# ETHERNET.net
KiCad netlist of a schematic drawn in Altium Designer
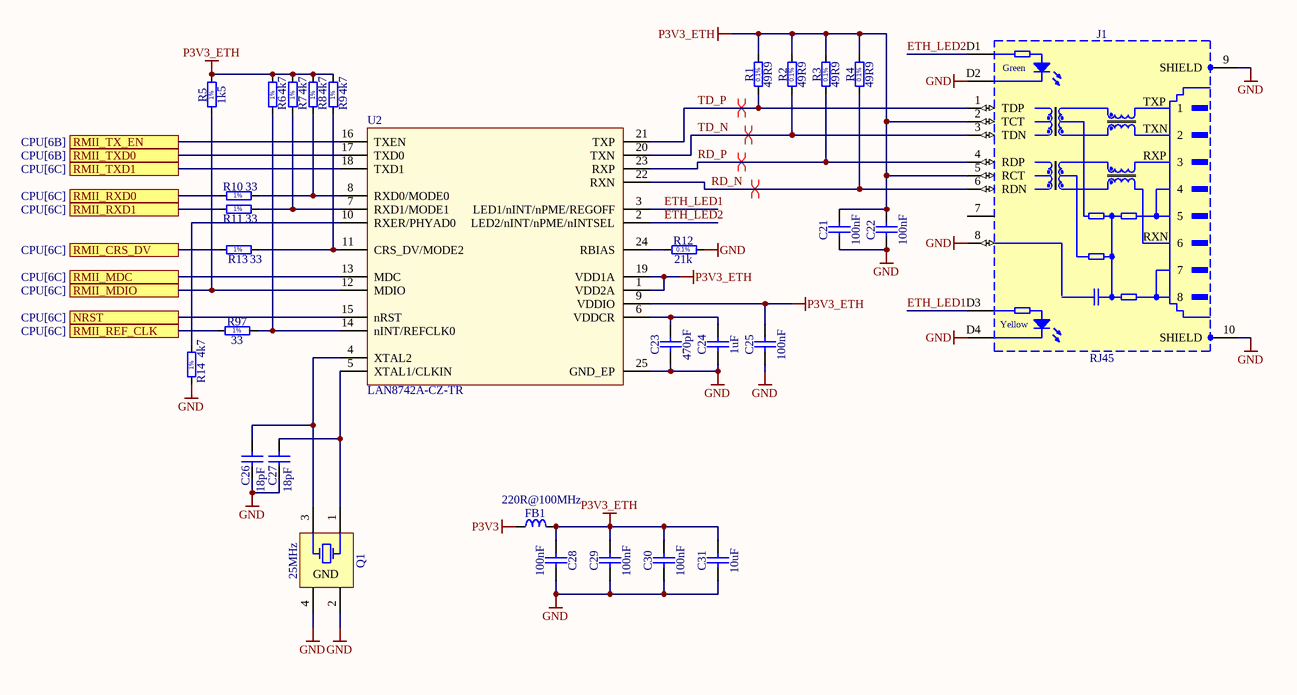
[diagram p0: ETHERNET.SchDoc]

(export (version "E")
  (design (tool "Eeschema 10.0.6"))
  (components
    (comp (ref "C21")
      (value "100nF")
      (footprint "CAPC1005X55N")
      (description "Non-polarised capacitor")
      (fields
        (field (name "PART NUMBER") "CC0402_100NF_16V_10%_X5R")
        (field (name "VOLTAGE") "16V")
        (field (name "AUTHOR") "CERN DEM JLC")
      )
      (libsource (lib "Capacitors") (part "Capacitor - non polarized"))
    )
    (comp (ref "C22")
      (value "100nF")
      (footprint "CAPC1005X55N")
      (description "Non-polarised capacitor")
      (fields
        (field (name "PART NUMBER") "CC0402_100NF_16V_10%_X5R")
        (field (name "VOLTAGE") "16V")
        (field (name "AUTHOR") "CERN DEM JLC")
      )
      (libsource (lib "Capacitors") (part "Capacitor - non polarized"))
    )
    (comp (ref "C23")
      (value "470pF")
      (footprint "CAPC1005X55N")
      (description "Non-polarised capacitor")
      (fields
        (field (name "PART NUMBER") "CC0402_470PF_50V_10%_X7R")
        (field (name "VOLTAGE") "50V")
        (field (name "AUTHOR") "CERN DEM JLC")
      )
      (libsource (lib "Capacitors") (part "Capacitor - non polarized"))
    )
    (comp (ref "C24")
      (value "1uF")
      (footprint "CAPC1005X55N")
      (description "Non-polarised capacitor")
      (fields
        (field (name "PART NUMBER") "CC0402_1UF_16V_10%_X5R")
        (field (name "VOLTAGE") "16V")
        (field (name "AUTHOR") "CERN DEM JLC")
      )
      (libsource (lib "Capacitors") (part "Capacitor - non polarized"))
    )
    (comp (ref "C25")
      (value "100nF")
      (footprint "CAPC1005X55N")
      (description "Non-polarised capacitor")
      (fields
        (field (name "PART NUMBER") "CC0402_100NF_16V_10%_X5R")
        (field (name "VOLTAGE") "16V")
        (field (name "AUTHOR") "CERN DEM JLC")
      )
      (libsource (lib "Capacitors") (part "Capacitor - non polarized"))
    )
    (comp (ref "C26")
      (value "18pF")
      (footprint "CAPC1005X55N")
      (description "Non-polarised capacitor")
      (fields
        (field (name "PART NUMBER") "CC0402_18PF_50V_5%_C0G")
        (field (name "VOLTAGE") "50V")
        (field (name "AUTHOR") "CERN DEM JLC")
      )
      (libsource (lib "Capacitors") (part "Capacitor - non polarized"))
    )
    (comp (ref "C27")
      (value "18pF")
      (footprint "CAPC1005X55N")
      (description "Non-polarised capacitor")
      (fields
        (field (name "PART NUMBER") "CC0402_18PF_50V_5%_C0G")
        (field (name "VOLTAGE") "50V")
        (field (name "AUTHOR") "CERN DEM JLC")
      )
      (libsource (lib "Capacitors") (part "Capacitor - non polarized"))
    )
    (comp (ref "C28")
      (value "100nF")
      (footprint "CAPC1005X55N")
      (description "Non-polarised capacitor")
      (fields
        (field (name "PART NUMBER") "CC0402_100NF_16V_10%_X5R")
        (field (name "VOLTAGE") "16V")
        (field (name "AUTHOR") "CERN DEM JLC")
      )
      (libsource (lib "Capacitors") (part "Capacitor - non polarized"))
    )
    (comp (ref "C29")
      (value "100nF")
      (footprint "CAPC1005X55N")
      (description "Non-polarised capacitor")
      (fields
        (field (name "PART NUMBER") "CC0402_100NF_16V_10%_X5R")
        (field (name "VOLTAGE") "16V")
        (field (name "AUTHOR") "CERN DEM JLC")
      )
      (libsource (lib "Capacitors") (part "Capacitor - non polarized"))
    )
    (comp (ref "C30")
      (value "100nF")
      (footprint "CAPC1005X55N")
      (description "Non-polarised capacitor")
      (fields
        (field (name "PART NUMBER") "CC0402_100NF_16V_10%_X5R")
        (field (name "VOLTAGE") "16V")
        (field (name "AUTHOR") "CERN DEM JLC")
      )
      (libsource (lib "Capacitors") (part "Capacitor - non polarized"))
    )
    (comp (ref "C31")
      (value "10uF")
      (footprint "CAPC2012X135N")
      (description "Non-polarised capacitor")
      (fields
        (field (name "PART NUMBER") "CC0805_10UF_16V_10%_X5R")
        (field (name "VOLTAGE") "16V")
        (field (name "AUTHOR") "CERN DEM JLC")
      )
      (libsource (lib "Capacitors") (part "Capacitor - non polarized"))
    )
    (comp (ref "FB1")
      (value "220R@100MHz")
      (footprint "INDC2012X105N")
      (description "Inductor")
      (fields
        (field (name "PART NUMBER") "IND0805_MURATA_BLM21PG221SN1D")
        (field (name "POWER") "2A")
        (field (name "AUTHOR") "CERN DEM JLC")
      )
      (libsource (lib "Inductors & Transformers") (part "Inductor"))
    )
    (comp (ref "J1")
      (value "RJ45")
      (footprint "TYCO_5-6605308-1")
      (fields
        (field (name "PART NUMBER") "TYCO_5-6605308-1")
        (field (name "MANUFACTURER") "TYCO ELECTRONICS")
        (field (name "MANUFACTURER PART NUMBER") "5-6605308-1")
        (field (name "AUTHOR") "CERN DEM JLC")
      )
      (libsource (lib "Connectors") (part "TYCO_5-6605308-1"))
    )
    (comp (ref "Q1")
      (value "25MHz")
      (footprint "XTAL_EPSON_TSX-3225")
      (description "Crystal 4 pins 1=XTAL Control 2=GND3=XTAL 4=GND")
      (fields
        (field (name "PART NUMBER") "XTAL_25MHZ_EPSON_TSX-3225 25.0000MF10Z-AC")
        (field (name "MANUFACTURER") "EPSON")
        (field (name "AUTHOR") "CERN DEM JLC")
      )
      (libsource (lib "ICs And Semiconductors") (part "Quartz Crystal 1X 2GND 3X 4GND"))
    )
    (comp (ref "R1")
      (value "49R9")
      (footprint "RESC1005X35N")
      (description "Resistor - 0.1%")
      (fields
        (field (name "PART NUMBER") "R0402_49R9_0.1%_0.063W_25PPM")
        (field (name "POWER") "0.063W")
        (field (name "AUTHOR") "CERN DEM JMW")
      )
      (libsource (lib "Resistors") (part "Resistor - 0.1%"))
    )
    (comp (ref "R2")
      (value "49R9")
      (footprint "RESC1005X35N")
      (description "Resistor - 0.1%")
      (fields
        (field (name "PART NUMBER") "R0402_49R9_0.1%_0.063W_25PPM")
        (field (name "POWER") "0.063W")
        (field (name "AUTHOR") "CERN DEM JMW")
      )
      (libsource (lib "Resistors") (part "Resistor - 0.1%"))
    )
    (comp (ref "R3")
      (value "49R9")
      (footprint "RESC1005X35N")
      (description "Resistor - 0.1%")
      (fields
        (field (name "PART NUMBER") "R0402_49R9_0.1%_0.063W_25PPM")
        (field (name "POWER") "0.063W")
        (field (name "AUTHOR") "CERN DEM JMW")
      )
      (libsource (lib "Resistors") (part "Resistor - 0.1%"))
    )
    (comp (ref "R4")
      (value "49R9")
      (footprint "RESC1005X35N")
      (description "Resistor - 0.1%")
      (fields
        (field (name "PART NUMBER") "R0402_49R9_0.1%_0.063W_25PPM")
        (field (name "POWER") "0.063W")
        (field (name "AUTHOR") "CERN DEM JMW")
      )
      (libsource (lib "Resistors") (part "Resistor - 0.1%"))
    )
    (comp (ref "R5")
      (value "1k5")
      (footprint "RESC1005X40N")
      (description "Resistor - 1%")
      (fields
        (field (name "PART NUMBER") "R0402_1K5_1%_0.0625W_100PPM")
        (field (name "POWER") "0.0625W")
        (field (name "AUTHOR") "CERN DEM JLC")
      )
      (libsource (lib "Resistors") (part "Resistor - 1%"))
    )
    (comp (ref "R6")
      (value "4k7")
      (footprint "RESC1005X40N")
      (description "Resistor - 1%")
      (fields
        (field (name "PART NUMBER") "R0402_4K7_1%_0.0625W_100PPM")
        (field (name "POWER") "0.0625W")
        (field (name "AUTHOR") "CERN DEM JLC")
      )
      (libsource (lib "Resistors") (part "Resistor - 1%"))
    )
    (comp (ref "R7")
      (value "4k7")
      (footprint "RESC1005X40N")
      (description "Resistor - 1%")
      (fields
        (field (name "PART NUMBER") "R0402_4K7_1%_0.0625W_100PPM")
        (field (name "POWER") "0.0625W")
        (field (name "AUTHOR") "CERN DEM JLC")
      )
      (libsource (lib "Resistors") (part "Resistor - 1%"))
    )
    (comp (ref "R8")
      (value "4k7")
      (footprint "RESC1005X40N")
      (description "Resistor - 1%")
      (fields
        (field (name "PART NUMBER") "R0402_4K7_1%_0.0625W_100PPM")
        (field (name "POWER") "0.0625W")
        (field (name "AUTHOR") "CERN DEM JLC")
      )
      (libsource (lib "Resistors") (part "Resistor - 1%"))
    )
    (comp (ref "R9")
      (value "4k7")
      (footprint "RESC1005X40N")
      (description "Resistor - 1%")
      (fields
        (field (name "PART NUMBER") "R0402_4K7_1%_0.0625W_100PPM")
        (field (name "POWER") "0.0625W")
        (field (name "AUTHOR") "CERN DEM JLC")
      )
      (libsource (lib "Resistors") (part "Resistor - 1%"))
    )
    (comp (ref "R10")
      (value "33")
      (footprint "RESC1005X40N")
      (description "Resistor - 1%")
      (fields
        (field (name "PART NUMBER") "R0402_33R_1%_0.0625W_100PPM")
        (field (name "POWER") "0.0625W")
        (field (name "AUTHOR") "CERN DEM JLC")
      )
      (libsource (lib "Resistors") (part "Resistor - 1%"))
    )
    (comp (ref "R11")
      (value "33")
      (footprint "RESC1005X40N")
      (description "Resistor - 1%")
      (fields
        (field (name "PART NUMBER") "R0402_33R_1%_0.0625W_100PPM")
        (field (name "POWER") "0.0625W")
        (field (name "AUTHOR") "CERN DEM JLC")
      )
      (libsource (lib "Resistors") (part "Resistor - 1%"))
    )
    (comp (ref "R12")
      (value "21k")
      (footprint "RESC1608X55N")
      (description "Resistor - 0.1%")
      (fields
        (field (name "PART NUMBER") "R0603_21K_0.1%_0.063W_10PPM")
        (field (name "POWER") "0.063W")
        (field (name "AUTHOR") "CERN DEM JLC")
      )
      (libsource (lib "Resistors") (part "Resistor - 0.1%"))
    )
    (comp (ref "R13")
      (value "33")
      (footprint "RESC1005X40N")
      (description "Resistor - 1%")
      (fields
        (field (name "PART NUMBER") "R0402_33R_1%_0.0625W_100PPM")
        (field (name "POWER") "0.0625W")
        (field (name "AUTHOR") "CERN DEM JLC")
      )
      (libsource (lib "Resistors") (part "Resistor - 1%"))
    )
    (comp (ref "R14")
      (value "4k7")
      (footprint "RESC1005X40N")
      (description "Resistor - 1%")
      (fields
        (field (name "PART NUMBER") "R0402_4K7_1%_0.0625W_100PPM")
        (field (name "POWER") "0.0625W")
        (field (name "AUTHOR") "CERN DEM JLC")
      )
      (libsource (lib "Resistors") (part "Resistor - 1%"))
    )
    (comp (ref "R97")
      (value "33")
      (footprint "RESC1005X40N")
      (description "Resistor - 1%")
      (fields
        (field (name "PART NUMBER") "R0402_33R_1%_0.0625W_100PPM")
        (field (name "POWER") "0.0625W")
        (field (name "AUTHOR") "CERN DEM JLC")
      )
      (libsource (lib "Resistors") (part "Resistor - 1%"))
    )
    (comp (ref "U2")
      (value "LAN8742A-CZ-TR")
      (footprint "QFN50P400X400X80-25N-S225")
      (libsource (lib "MB1137") (part "LAN8742A-CZ-TR"))
    )
  )
  (nets
    (net (code "1") (name "/ETH_LED1") (class "Default")
      (node (ref "J1") (pin "D3") (pinfunction "D3_D3") (pintype "passive"))
      (node (ref "U2") (pin "3") (pinfunction "LED1/nINT/nPME/REGOFF_3") (pintype "passive"))
    )
    (net (code "2") (name "/ETH_LED2") (class "Default")
      (node (ref "J1") (pin "D1") (pinfunction "D1_D1") (pintype "passive"))
      (node (ref "U2") (pin "2") (pinfunction "LED2/nINT/nPME/nINTSEL_2") (pintype "passive"))
    )
    (net (code "3") (name "/NRST") (class "Default")
      (node (ref "U2") (pin "15") (pinfunction "nRST_15") (pintype "passive"))
    )
    (net (code "4") (name "/RD_N") (class "Default")
      (node (ref "J1") (pin "6") (pinfunction "RDN_6") (pintype "bidirectional"))
      (node (ref "R4") (pin "1") (pinfunction "1_1") (pintype "passive"))
      (node (ref "U2") (pin "22") (pinfunction "RXN_22") (pintype "passive"))
    )
    (net (code "5") (name "/RD_P") (class "Default")
      (node (ref "J1") (pin "4") (pinfunction "RDP_4") (pintype "bidirectional"))
      (node (ref "R3") (pin "1") (pinfunction "1_1") (pintype "passive"))
      (node (ref "U2") (pin "23") (pinfunction "RXP_23") (pintype "passive"))
    )
    (net (code "6") (name "/RMII_CRS_DV") (class "Default")
      (node (ref "R13") (pin "1") (pinfunction "1_1") (pintype "passive"))
    )
    (net (code "7") (name "/RMII_MDC") (class "Default")
      (node (ref "U2") (pin "13") (pinfunction "MDC_13") (pintype "passive"))
    )
    (net (code "8") (name "/RMII_MDIO") (class "Default")
      (node (ref "R5") (pin "1") (pinfunction "1_1") (pintype "passive"))
      (node (ref "U2") (pin "12") (pinfunction "MDIO_12") (pintype "passive"))
    )
    (net (code "9") (name "/RMII_REF_CLK") (class "Default")
      (node (ref "R97") (pin "1") (pinfunction "1_1") (pintype "passive"))
    )
    (net (code "10") (name "/RMII_RXD0") (class "Default")
      (node (ref "R10") (pin "1") (pinfunction "1_1") (pintype "passive"))
    )
    (net (code "11") (name "/RMII_RXD1") (class "Default")
      (node (ref "R11") (pin "1") (pinfunction "1_1") (pintype "passive"))
    )
    (net (code "12") (name "/RMII_TXD0") (class "Default")
      (node (ref "U2") (pin "17") (pinfunction "TXD0_17") (pintype "passive"))
    )
    (net (code "13") (name "/RMII_TXD1") (class "Default")
      (node (ref "U2") (pin "18") (pinfunction "TXD1_18") (pintype "passive"))
    )
    (net (code "14") (name "/RMII_TX_EN") (class "Default")
      (node (ref "U2") (pin "16") (pinfunction "TXEN_16") (pintype "passive"))
    )
    (net (code "15") (name "/TD_N") (class "Default")
      (node (ref "J1") (pin "3") (pinfunction "TDN_3") (pintype "bidirectional"))
      (node (ref "R2") (pin "1") (pinfunction "1_1") (pintype "passive"))
      (node (ref "U2") (pin "20") (pinfunction "TXN_20") (pintype "passive"))
    )
    (net (code "16") (name "/TD_P") (class "Default")
      (node (ref "J1") (pin "1") (pinfunction "TDP_1") (pintype "bidirectional"))
      (node (ref "R1") (pin "1") (pinfunction "1_1") (pintype "passive"))
      (node (ref "U2") (pin "21") (pinfunction "TXP_21") (pintype "passive"))
    )
    (net (code "17") (name "GND") (class "Default")
      (node (ref "C21") (pin "1") (pinfunction "1_1") (pintype "passive"))
      (node (ref "C22") (pin "1") (pinfunction "1_1") (pintype "passive"))
      (node (ref "C23") (pin "1") (pinfunction "1_1") (pintype "passive"))
      (node (ref "C24") (pin "1") (pinfunction "1_1") (pintype "passive"))
      (node (ref "C25") (pin "1") (pinfunction "1_1") (pintype "passive"))
      (node (ref "C26") (pin "1") (pinfunction "1_1") (pintype "passive"))
      (node (ref "C27") (pin "1") (pinfunction "1_1") (pintype "passive"))
      (node (ref "C28") (pin "2") (pinfunction "2_2") (pintype "passive"))
      (node (ref "C29") (pin "1") (pinfunction "1_1") (pintype "passive"))
      (node (ref "C30") (pin "1") (pinfunction "1_1") (pintype "passive"))
      (node (ref "C31") (pin "1") (pinfunction "1_1") (pintype "passive"))
      (node (ref "J1") (pin "10") (pinfunction "SHIELD_10") (pintype "power_in"))
      (node (ref "J1") (pin "8") (pinfunction "8_8") (pintype "bidirectional"))
      (node (ref "J1") (pin "9") (pinfunction "SHIELD_9") (pintype "power_in"))
      (node (ref "J1") (pin "D2") (pinfunction "D2_D2") (pintype "passive"))
      (node (ref "J1") (pin "D4") (pinfunction "D4_D4") (pintype "passive"))
      (node (ref "Q1") (pin "2") (pinfunction "GND_2") (pintype "power_in"))
      (node (ref "Q1") (pin "4") (pinfunction "GND_4") (pintype "power_in"))
      (node (ref "R12") (pin "2") (pinfunction "2_2") (pintype "passive"))
      (node (ref "R14") (pin "1") (pinfunction "1_1") (pintype "passive"))
      (node (ref "U2") (pin "25") (pinfunction "GND_EP_25") (pintype "passive"))
    )
    (net (code "18") (name "Net-(U2-CRS_DV{slash}MODE2)") (class "Default")
      (node (ref "R13") (pin "2") (pinfunction "2_2") (pintype "passive"))
      (node (ref "R9") (pin "1") (pinfunction "1_1") (pintype "passive"))
      (node (ref "U2") (pin "11") (pinfunction "CRS_DV/MODE2_11") (pintype "passive"))
    )
    (net (code "19") (name "Net-(U2-RBIAS)") (class "Default")
      (node (ref "R12") (pin "1") (pinfunction "1_1") (pintype "passive"))
      (node (ref "U2") (pin "24") (pinfunction "RBIAS_24") (pintype "passive"))
    )
    (net (code "20") (name "Net-(U2-RXD0{slash}MODE0)") (class "Default")
      (node (ref "R10") (pin "2") (pinfunction "2_2") (pintype "passive"))
      (node (ref "R8") (pin "1") (pinfunction "1_1") (pintype "passive"))
      (node (ref "U2") (pin "8") (pinfunction "RXD0/MODE0_8") (pintype "passive"))
    )
    (net (code "21") (name "Net-(U2-RXD1{slash}MODE1)") (class "Default")
      (node (ref "R11") (pin "2") (pinfunction "2_2") (pintype "passive"))
      (node (ref "R7") (pin "1") (pinfunction "1_1") (pintype "passive"))
      (node (ref "U2") (pin "7") (pinfunction "RXD1/MODE1_7") (pintype "passive"))
    )
    (net (code "22") (name "Net-(U2-RXER{slash}PHYAD0)") (class "Default")
      (node (ref "R14") (pin "2") (pinfunction "2_2") (pintype "passive"))
      (node (ref "U2") (pin "10") (pinfunction "RXER/PHYAD0_10") (pintype "passive"))
    )
    (net (code "23") (name "Net-(U2-VDDCR)") (class "Default")
      (node (ref "C23") (pin "2") (pinfunction "2_2") (pintype "passive"))
      (node (ref "C24") (pin "2") (pinfunction "2_2") (pintype "passive"))
      (node (ref "U2") (pin "6") (pinfunction "VDDCR_6") (pintype "passive"))
    )
    (net (code "24") (name "Net-(U2-XTAL1{slash}CLKIN)") (class "Default")
      (node (ref "C27") (pin "2") (pinfunction "2_2") (pintype "passive"))
      (node (ref "Q1") (pin "1") (pinfunction "X_1") (pintype "passive"))
      (node (ref "U2") (pin "5") (pinfunction "XTAL1/CLKIN_5") (pintype "passive"))
    )
    (net (code "25") (name "Net-(U2-XTAL2)") (class "Default")
      (node (ref "C26") (pin "2") (pinfunction "2_2") (pintype "passive"))
      (node (ref "Q1") (pin "3") (pinfunction "X_3") (pintype "passive"))
      (node (ref "U2") (pin "4") (pinfunction "XTAL2_4") (pintype "passive"))
    )
    (net (code "26") (name "Net-(U2-nINT{slash}REFCLK0)") (class "Default")
      (node (ref "R6") (pin "1") (pinfunction "1_1") (pintype "passive"))
      (node (ref "R97") (pin "2") (pinfunction "2_2") (pintype "passive"))
      (node (ref "U2") (pin "14") (pinfunction "nINT/REFCLK0_14") (pintype "passive"))
    )
    (net (code "27") (name "P3V3") (class "Default")
      (node (ref "FB1") (pin "1") (pinfunction "1_1") (pintype "passive"))
    )
    (net (code "28") (name "P3V3_ETH") (class "Default")
      (node (ref "C21") (pin "2") (pinfunction "2_2") (pintype "passive"))
      (node (ref "C22") (pin "2") (pinfunction "2_2") (pintype "passive"))
      (node (ref "C25") (pin "2") (pinfunction "2_2") (pintype "passive"))
      (node (ref "C28") (pin "1") (pinfunction "1_1") (pintype "passive"))
      (node (ref "C29") (pin "2") (pinfunction "2_2") (pintype "passive"))
      (node (ref "C30") (pin "2") (pinfunction "2_2") (pintype "passive"))
      (node (ref "C31") (pin "2") (pinfunction "2_2") (pintype "passive"))
      (node (ref "FB1") (pin "2") (pinfunction "2_2") (pintype "passive"))
      (node (ref "J1") (pin "2") (pinfunction "TCT_2") (pintype "bidirectional"))
      (node (ref "J1") (pin "5") (pinfunction "RCT_5") (pintype "bidirectional"))
      (node (ref "R1") (pin "2") (pinfunction "2_2") (pintype "passive"))
      (node (ref "R2") (pin "2") (pinfunction "2_2") (pintype "passive"))
      (node (ref "R3") (pin "2") (pinfunction "2_2") (pintype "passive"))
      (node (ref "R4") (pin "2") (pinfunction "2_2") (pintype "passive"))
      (node (ref "R5") (pin "2") (pinfunction "2_2") (pintype "passive"))
      (node (ref "R6") (pin "2") (pinfunction "2_2") (pintype "passive"))
      (node (ref "R7") (pin "2") (pinfunction "2_2") (pintype "passive"))
      (node (ref "R8") (pin "2") (pinfunction "2_2") (pintype "passive"))
      (node (ref "R9") (pin "2") (pinfunction "2_2") (pintype "passive"))
      (node (ref "U2") (pin "1") (pinfunction "VDD2A_1") (pintype "passive"))
      (node (ref "U2") (pin "19") (pinfunction "VDD1A_19") (pintype "passive"))
      (node (ref "U2") (pin "9") (pinfunction "VDDIO_9") (pintype "passive"))
    )
    (net (code "29") (name "unconnected-(J1-Pad7)") (class "Default")
      (node (ref "J1") (pin "7") (pinfunction "7_7") (pintype "passive"))
    )
  )
)
